# buck.net
KiCad netlist of a schematic drawn in EAGLE
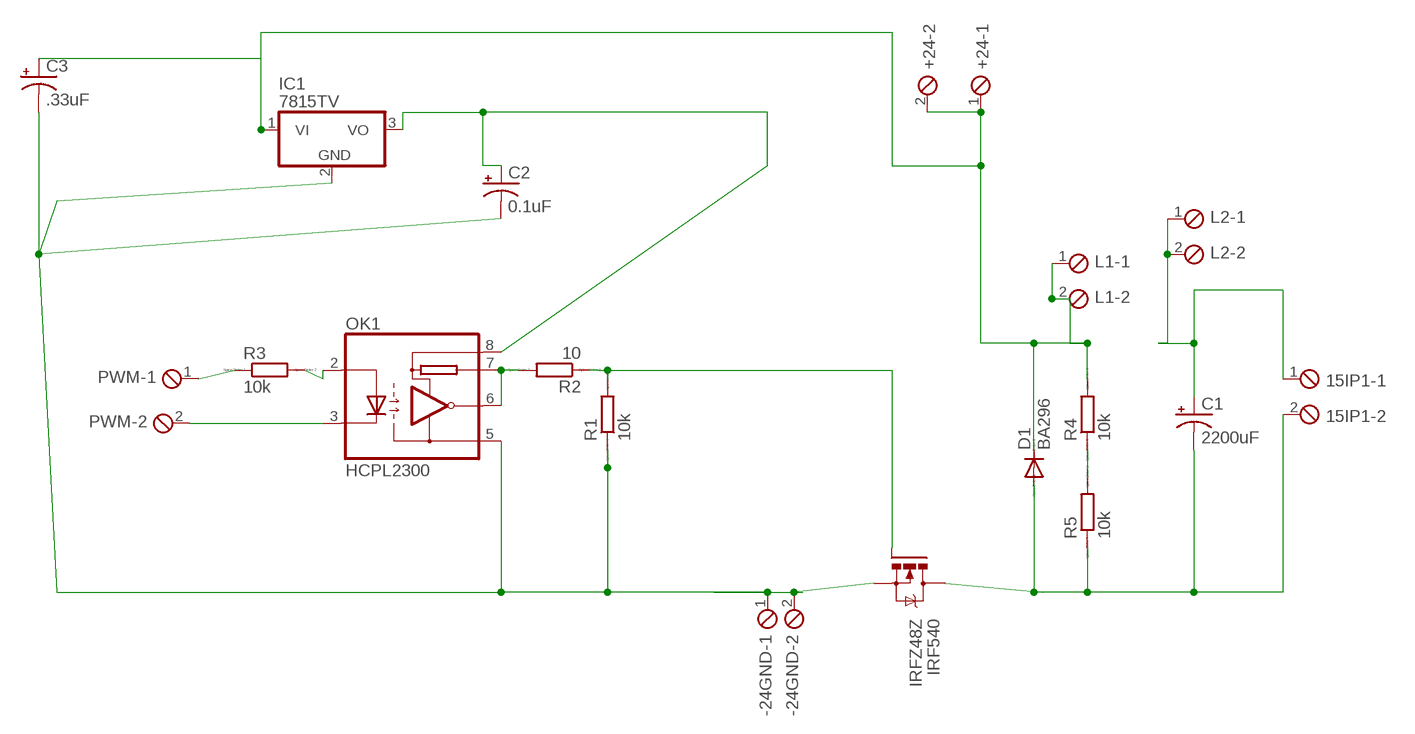
[diagram p0: schematic, sheet 1]

(export (version "E")
  (design (tool "Eeschema 10.0.6"))
  (components
    (comp (ref "+24")
      (value "MPT2")
      (footprint "eagle-import:2POL254")
      (libsource (lib "eagle-import") (part "MPT2"))
    )
    (comp (ref "-24GND")
      (value "MPT2")
      (footprint "eagle-import:2POL254")
      (libsource (lib "eagle-import") (part "MPT2"))
    )
    (comp (ref "15IP1")
      (value "MPT2")
      (footprint "eagle-import:2POL254")
      (libsource (lib "eagle-import") (part "MPT2"))
    )
    (comp (ref "C1")
      (value "2200uF")
      (footprint "eagle-import:CPOL-RADIAL-5MM-10MM")
      (libsource (lib "eagle-import") (part "1000UF-RADIAL-5MM-25V-20%"))
    )
    (comp (ref "C2")
      (value "0.1uF")
      (footprint "eagle-import:CPOL-RADIAL-5MM-10MM")
      (libsource (lib "eagle-import") (part "1000UF-RADIAL-5MM-25V-20%"))
    )
    (comp (ref "C3")
      (value ".33uF")
      (footprint "eagle-import:CPOL-RADIAL-5MM-10MM")
      (libsource (lib "eagle-import") (part "1000UF-RADIAL-5MM-25V-20%"))
    )
    (comp (ref "D1")
      (value "BA296")
      (footprint "eagle-import:P2-15")
      (libsource (lib "eagle-import") (part "BA296"))
    )
    (comp (ref "IC1")
      (value "7815TV")
      (footprint "eagle-import:TO220V")
      (libsource (lib "eagle-import") (part "78TV15"))
    )
    (comp (ref "IRF540")
      (value "IRFZ48Z")
      (footprint "eagle-import:TO220BH")
      (libsource (lib "eagle-import") (part "IRFZ48Z"))
    )
    (comp (ref "L1")
      (value "MPT2")
      (footprint "eagle-import:2POL254")
      (libsource (lib "eagle-import") (part "MPT2"))
    )
    (comp (ref "L2")
      (value "MPT2")
      (footprint "eagle-import:2POL254")
      (libsource (lib "eagle-import") (part "MPT2"))
    )
    (comp (ref "OK1")
      (value "HCPL2300")
      (footprint "eagle-import:DIL08")
      (fields (field (name "MF") "AGILENT TECHNOLOGIES") (field (name "MPN") "HCPL-2300-000E"))
      (libsource (lib "eagle-import") (part "HCPL2300"))
    )
    (comp (ref "PWM")
      (value "MPT2")
      (footprint "eagle-import:2POL254")
      (libsource (lib "eagle-import") (part "MPT2"))
    )
    (comp (ref "R1")
      (value "10k")
      (footprint "eagle-import:0204_7")
      (libsource (lib "eagle-import") (part "R0204/7"))
    )
    (comp (ref "R2")
      (value "10")
      (footprint "eagle-import:0204_7")
      (libsource (lib "eagle-import") (part "R0204/7"))
    )
    (comp (ref "R3")
      (value "10k")
      (footprint "eagle-import:0204_7")
      (libsource (lib "eagle-import") (part "R0204/7"))
    )
    (comp (ref "R4")
      (value "10k")
      (footprint "eagle-import:0204_7")
      (libsource (lib "eagle-import") (part "R0204/7"))
    )
    (comp (ref "R5")
      (value "10k")
      (footprint "eagle-import:0204_7")
      (libsource (lib "eagle-import") (part "R0204/7"))
    )
  )
  (nets
    (net (code "1") (name "Net-(+24B-1)") (class "Default")
      (node (ref "+24") (pin "1") (pinfunction "1_1") (pintype "passive"))
      (node (ref "+24") (pin "2") (pinfunction "1_2") (pintype "passive"))
      (node (ref "C3") (pin "+") (pinfunction "+_+") (pintype "passive"))
      (node (ref "D1") (pin "C") (pinfunction "C_C") (pintype "passive"))
      (node (ref "IC1") (pin "1") (pinfunction "VI_1") (pintype "input"))
      (node (ref "L1") (pin "1") (pinfunction "1_1") (pintype "passive"))
      (node (ref "L1") (pin "2") (pinfunction "1_2") (pintype "passive"))
      (node (ref "R4") (pin "2") (pinfunction "2_2") (pintype "passive"))
    )
    (net (code "2") (name "Net-(-24GNDB-1)") (class "Default")
      (node (ref "-24GND") (pin "1") (pinfunction "1_1") (pintype "passive"))
      (node (ref "-24GND") (pin "2") (pinfunction "1_2") (pintype "passive"))
      (node (ref "C2") (pin "-") (pinfunction "-_-") (pintype "passive"))
      (node (ref "C3") (pin "-") (pinfunction "-_-") (pintype "passive"))
      (node (ref "IC1") (pin "2") (pinfunction "GND_2") (pintype "passive"))
      (node (ref "IRF540") (pin "S") (pinfunction "S_S") (pintype "passive"))
      (node (ref "OK1") (pin "5") (pinfunction "GND_5") (pintype "passive"))
      (node (ref "R1") (pin "1") (pinfunction "1_1") (pintype "passive"))
    )
    (net (code "3") (name "Net-(15IP1B-1)") (class "Default")
      (node (ref "15IP1") (pin "2") (pinfunction "1_2") (pintype "passive"))
      (node (ref "C1") (pin "-") (pinfunction "-_-") (pintype "passive"))
      (node (ref "D1") (pin "A") (pinfunction "A_A") (pintype "passive"))
      (node (ref "IRF540") (pin "D") (pinfunction "D_D") (pintype "passive"))
      (node (ref "R5") (pin "1") (pinfunction "1_1") (pintype "passive"))
    )
    (net (code "4") (name "Net-(IC1-VO)") (class "Default")
      (node (ref "C2") (pin "+") (pinfunction "+_+") (pintype "passive"))
      (node (ref "IC1") (pin "3") (pinfunction "VO_3") (pintype "passive"))
      (node (ref "OK1") (pin "8") (pinfunction "VCC_8") (pintype "passive"))
    )
    (net (code "5") (name "Net-(IRF540-PadG)") (class "Default")
      (node (ref "IRF540") (pin "G") (pinfunction "G_G") (pintype "passive"))
      (node (ref "R1") (pin "2") (pinfunction "2_2") (pintype "passive"))
      (node (ref "R2") (pin "1") (pinfunction "1_1") (pintype "passive"))
    )
    (net (code "6") (name "Net-(L2B-1)") (class "Default")
      (node (ref "15IP1") (pin "1") (pinfunction "1_1") (pintype "passive"))
      (node (ref "C1") (pin "+") (pinfunction "+_+") (pintype "passive"))
      (node (ref "L2") (pin "1") (pinfunction "1_1") (pintype "passive"))
      (node (ref "L2") (pin "2") (pinfunction "1_2") (pintype "passive"))
    )
    (net (code "7") (name "Net-(OK1-A)") (class "Default")
      (node (ref "OK1") (pin "2") (pinfunction "A_2") (pintype "passive"))
      (node (ref "R3") (pin "2") (pinfunction "2_2") (pintype "passive"))
    )
    (net (code "8") (name "Net-(OK1-C)") (class "Default")
      (node (ref "OK1") (pin "3") (pinfunction "C_3") (pintype "passive"))
      (node (ref "PWM") (pin "2") (pinfunction "1_2") (pintype "passive"))
    )
    (net (code "9") (name "Net-(OK1-RL)") (class "Default")
      (node (ref "OK1") (pin "6") (pinfunction "VO_6") (pintype "passive"))
      (node (ref "OK1") (pin "7") (pinfunction "RL_7") (pintype "passive"))
      (node (ref "R2") (pin "2") (pinfunction "2_2") (pintype "passive"))
    )
    (net (code "10") (name "Net-(PWM-Pad1)") (class "Default")
      (node (ref "PWM") (pin "1") (pinfunction "1_1") (pintype "passive"))
      (node (ref "R3") (pin "1") (pinfunction "1_1") (pintype "passive"))
    )
    (net (code "11") (name "Net-(R4-Pad1)") (class "Default")
      (node (ref "R4") (pin "1") (pinfunction "1_1") (pintype "passive"))
      (node (ref "R5") (pin "2") (pinfunction "2_2") (pintype "passive"))
    )
  )
)
